# LM2576.net
KiCad netlist of a schematic drawn in Altium Designer
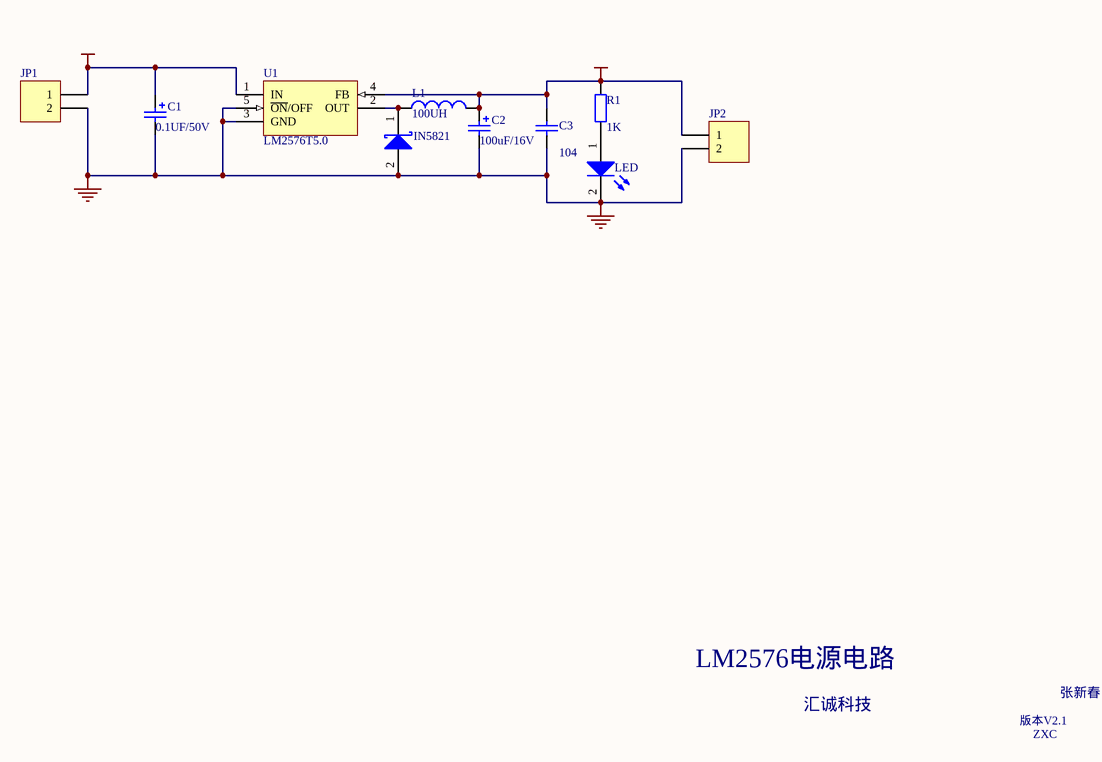
[diagram p0: LM2576电源电路.SchDoc]

(export (version "E")
  (design (tool "Eeschema 10.0.6"))
  (components
    (comp (ref "C1")
      (value "0.1UF/50V")
      (footprint "C-DJ-6")
      (description "电解电容")
      (fields (field (name "Comment") "DJDR") (field (name "PUBLISHER") "Altium Limited"))
      (libsource (lib "zxcourhc") (part "DJDR"))
    )
    (comp (ref "C2")
      (value "100uF/16V")
      (footprint "C-DJ-6")
      (description "电解电容")
      (fields (field (name "Comment") "DJDR") (field (name "PUBLISHER") "Altium Limited"))
      (libsource (lib "zxcourhc") (part "DJDR"))
    )
    (comp (ref "C3")
      (value "104")
      (footprint "CPDR")
      (description "瓷片电容")
      (fields (field (name "Comment") "CPDR") (field (name "PUBLISHER") "Altium Limited"))
      (libsource (lib "zxcourhc") (part "CPDR"))
    )
    (comp (ref "DS1")
      (value "LED")
      (footprint "LED_D")
      (description "发光二极管")
      (fields (field (name "PUBLISHER") "Altium Limited"))
      (libsource (lib "zxcourhc") (part "LED"))
    )
    (comp (ref "IN5821")
      (value "WY2JG")
      (footprint "ZCDZL")
      (description "稳压二级管")
      (fields (field (name "PUBLISHER") "Altium Limited"))
      (libsource (lib "zxcourhc") (part "WY2JG"))
    )
    (comp (ref "JP1")
      (value "PZ_2")
      (footprint "zxcourhc:JIKEKE")
      (description "排针——2")
      (fields (field (name "PUBLISHER") "Altium Limited"))
      (libsource (lib "") (part "PZ_2_1"))
    )
    (comp (ref "JP2")
      (value "PZ_2")
      (footprint "JIKEKE")
      (description "排针——2")
      (fields (field (name "PUBLISHER") "Altium Limited"))
      (libsource (lib "zxcourhc") (part "PZ_2"))
    )
    (comp (ref "L1")
      (value "100UH")
      (footprint "L_DG")
      (description "电感")
      (fields (field (name "Comment") "DG") (field (name "PUBLISHER") "Altium Limited"))
      (libsource (lib "zxcourhc") (part "DG"))
    )
    (comp (ref "R1")
      (value "1K")
      (footprint "RSE")
      (description "电阻")
      (fields (field (name "Comment") "Res") (field (name "PUBLISHER") "Altium Limited"))
      (libsource (lib "zxcourhc") (part "Res"))
    )
    (comp (ref "U1")
      (value "LM2576T5.0")
      (footprint "T05A")
      (description "Simple Switcher 3A Step Down Voltage Regulator")
      (fields (field (name "PUBLISHER") "Altium Limited"))
      (libsource (lib "NSC Power Mgt Switching Regulator") (part "LM2576HVT-3.3"))
    )
  )
  (nets
    (net (code "1") (name "+5V") (class "Default")
      (node (ref "C2") (pin "1") (pinfunction "1_1") (pintype "passive"))
      (node (ref "C3") (pin "2") (pinfunction "2_2") (pintype "passive"))
      (node (ref "JP2") (pin "1") (pinfunction "1_1") (pintype "passive"))
      (node (ref "L1") (pin "2") (pinfunction "2_2") (pintype "passive"))
      (node (ref "R1") (pin "2") (pinfunction "2_2") (pintype "passive"))
      (node (ref "U1") (pin "4") (pinfunction "FB_4") (pintype "input"))
    )
    (net (code "2") (name "GND") (class "Default")
      (node (ref "C1") (pin "2") (pinfunction "2_2") (pintype "passive"))
      (node (ref "C2") (pin "2") (pinfunction "2_2") (pintype "passive"))
      (node (ref "C3") (pin "1") (pinfunction "1_1") (pintype "passive"))
      (node (ref "DS1") (pin "2") (pinfunction "K_2") (pintype "passive"))
      (node (ref "IN5821") (pin "2") (pinfunction "K_2") (pintype "passive"))
      (node (ref "JP1") (pin "2") (pinfunction "2_2") (pintype "passive"))
      (node (ref "JP2") (pin "2") (pinfunction "2_2") (pintype "passive"))
      (node (ref "U1") (pin "3") (pinfunction "GND_3") (pintype "power_in"))
      (node (ref "U1") (pin "5") (pinfunction "~{ON}/OFF_5") (pintype "input"))
    )
    (net (code "3") (name "Net-(DS1-A)") (class "Default")
      (node (ref "DS1") (pin "1") (pinfunction "A_1") (pintype "passive"))
      (node (ref "R1") (pin "1") (pinfunction "1_1") (pintype "passive"))
    )
    (net (code "4") (name "Net-(IN5821-A)") (class "Default")
      (node (ref "IN5821") (pin "1") (pinfunction "A_1") (pintype "passive"))
      (node (ref "L1") (pin "1") (pinfunction "1_1") (pintype "passive"))
      (node (ref "U1") (pin "2") (pinfunction "OUT_2") (pintype "power_in"))
    )
    (net (code "5") (name "VCC") (class "Default")
      (node (ref "C1") (pin "1") (pinfunction "1_1") (pintype "passive"))
      (node (ref "JP1") (pin "1") (pinfunction "1_1") (pintype "passive"))
      (node (ref "U1") (pin "1") (pinfunction "IN_1") (pintype "power_in"))
    )
  )
)
